# Sheet1.net
KiCad netlist of a schematic drawn in Altium Designer
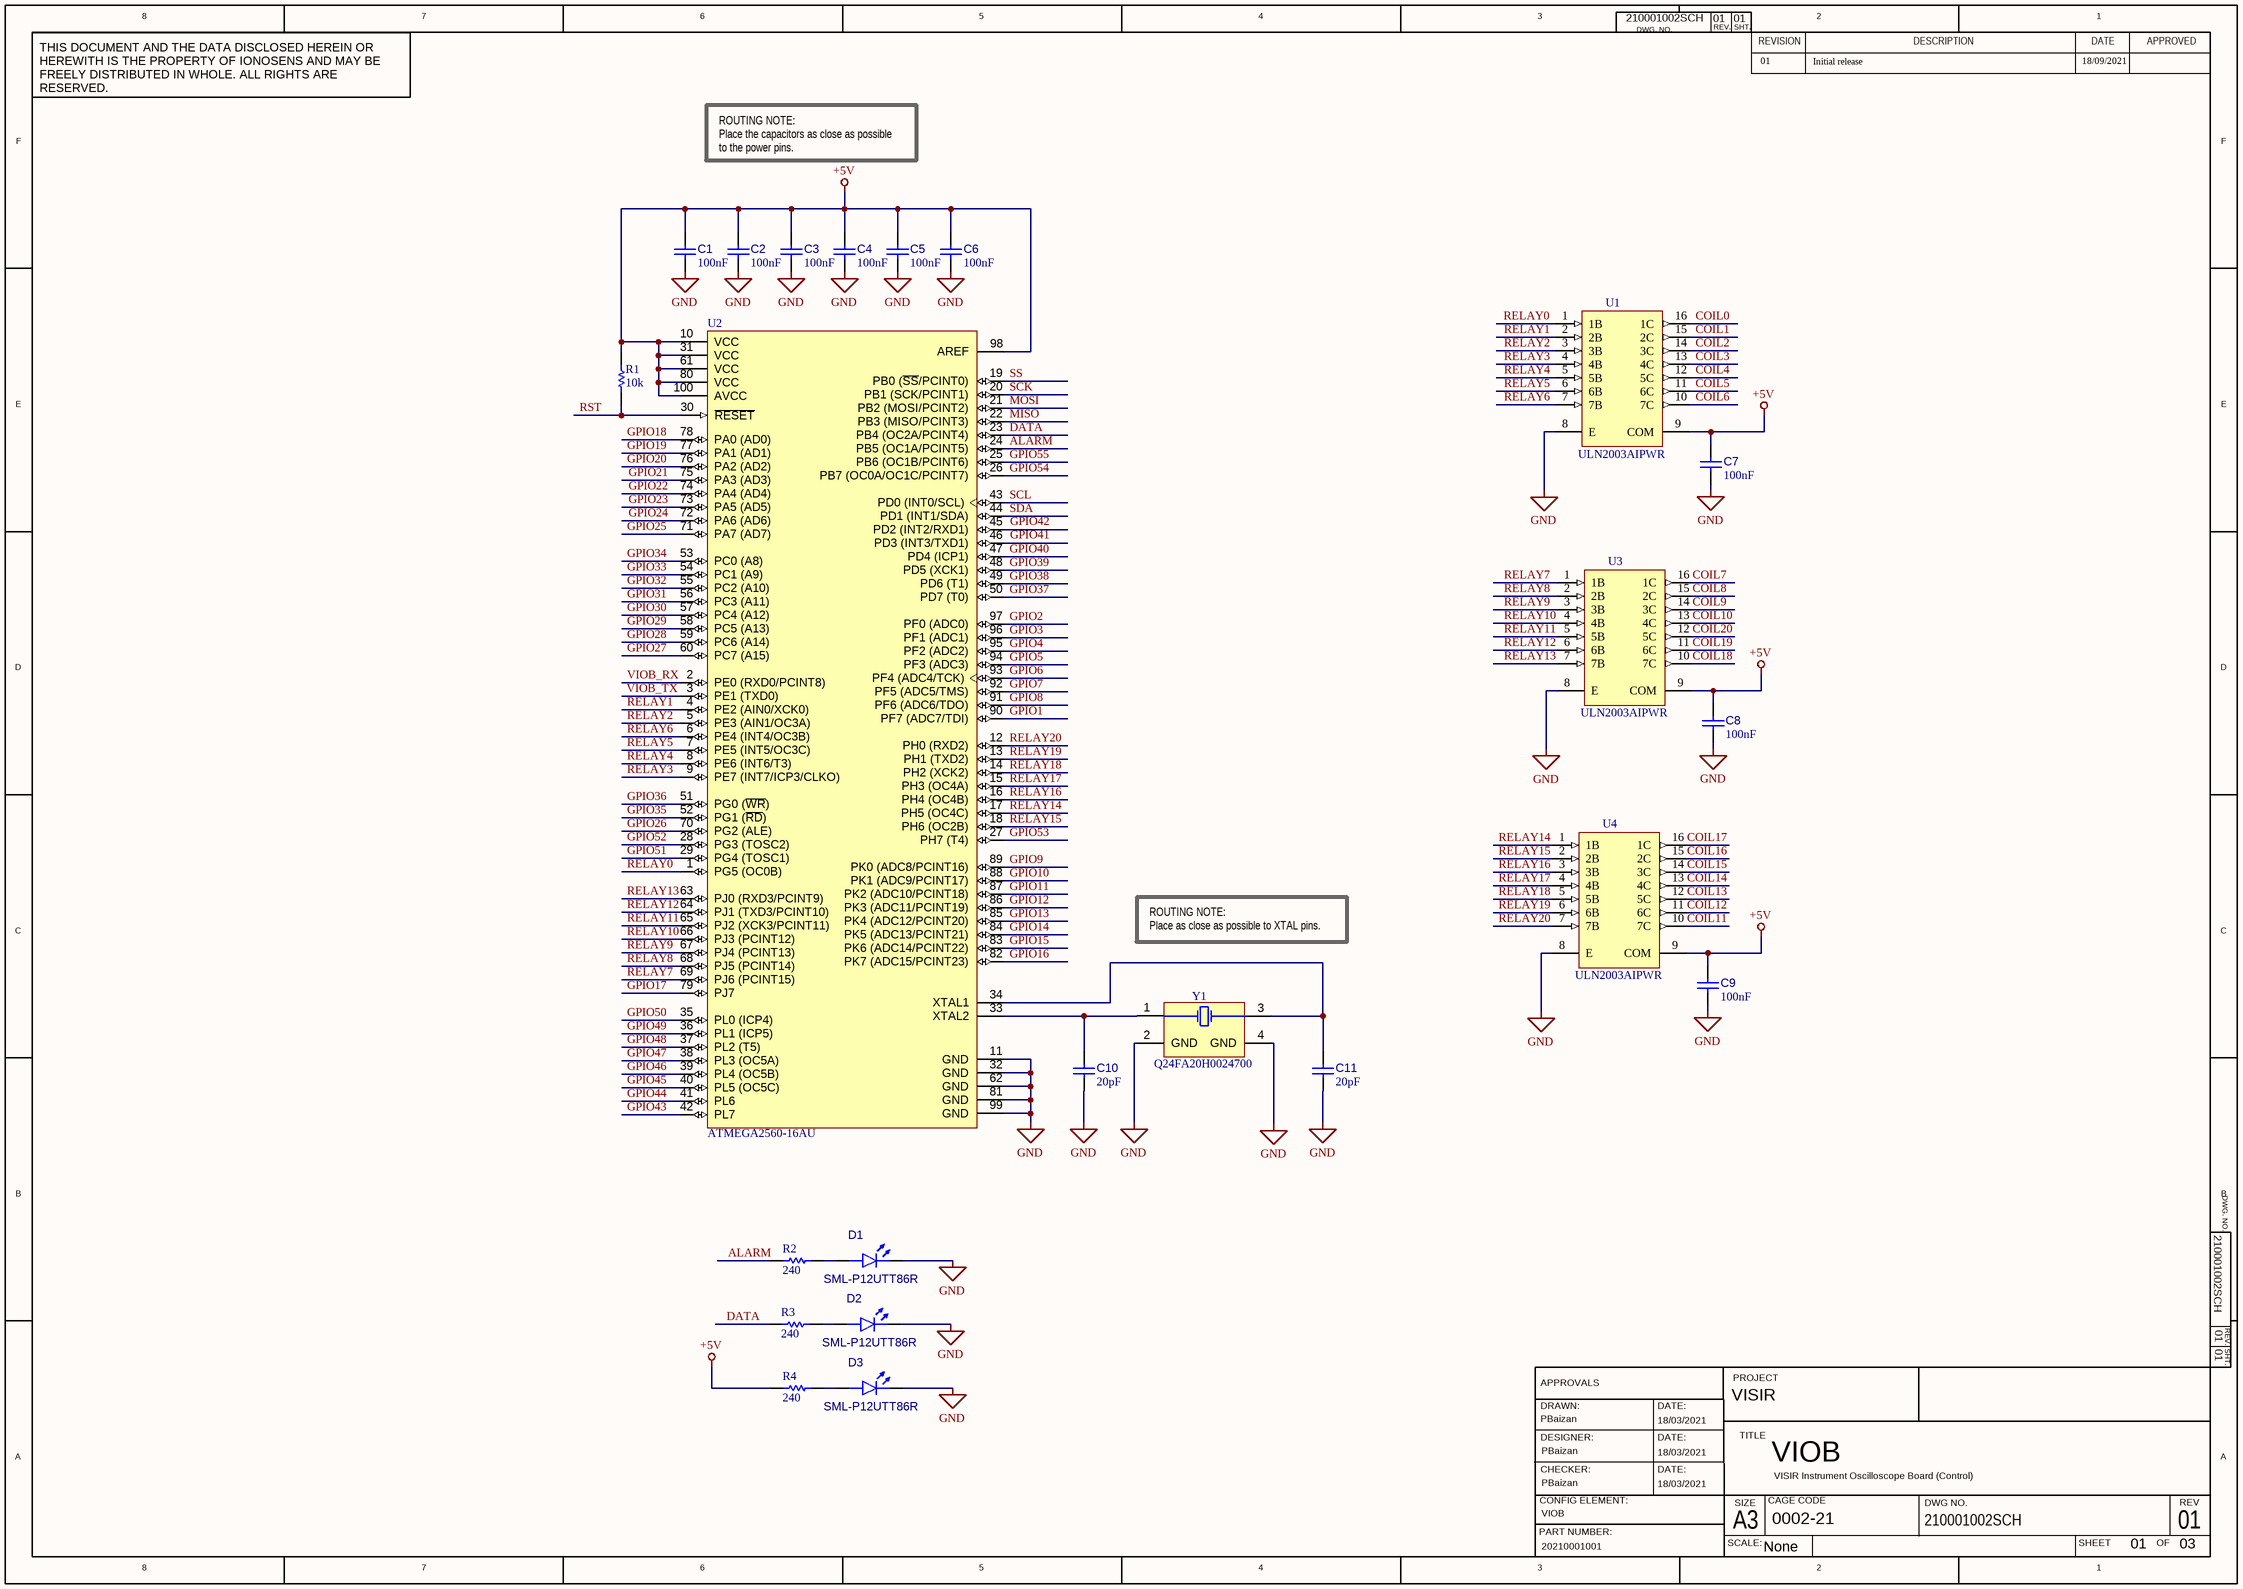
[diagram p0: Sheet1.SchDoc]

(export (version "E")
  (design (tool "Eeschema 10.0.6"))
  (components
    (comp (ref "C1")
      (value "100nF")
      (footprint "CAPC1005X06M")
      (description "Cap Ceramic 100nF 50V X7R 5% SMD 0402 125°C")
      (fields (field (name "TOLERANCE") "5%") (field (name "MANUFACTURER") "YAGEO"))
      (libsource (lib "<Company> Server") (part "CAP-NP-2"))
    )
    (comp (ref "C2")
      (value "100nF")
      (footprint "CAPC1005X06M")
      (description "Cap Ceramic 100nF 50V X7R 5% SMD 0402 125°C")
      (fields (field (name "TOLERANCE") "5%") (field (name "MANUFACTURER") "YAGEO"))
      (libsource (lib "<Company> Server") (part "CAP-NP-2"))
    )
    (comp (ref "C3")
      (value "100nF")
      (footprint "CAPC1005X06M")
      (description "Cap Ceramic 100nF 50V X7R 5% SMD 0402 125°C")
      (fields (field (name "TOLERANCE") "5%") (field (name "MANUFACTURER") "YAGEO"))
      (libsource (lib "<Company> Server") (part "CAP-NP-2"))
    )
    (comp (ref "C4")
      (value "100nF")
      (footprint "CAPC1005X06M")
      (description "Cap Ceramic 100nF 50V X7R 5% SMD 0402 125°C")
      (fields (field (name "TOLERANCE") "5%") (field (name "MANUFACTURER") "YAGEO"))
      (libsource (lib "<Company> Server") (part "CAP-NP-2"))
    )
    (comp (ref "C5")
      (value "100nF")
      (footprint "CAPC1005X06M")
      (description "Cap Ceramic 100nF 50V X7R 5% SMD 0402 125°C")
      (fields (field (name "TOLERANCE") "5%") (field (name "MANUFACTURER") "YAGEO"))
      (libsource (lib "<Company> Server") (part "CAP-NP-2"))
    )
    (comp (ref "C6")
      (value "100nF")
      (footprint "CAPC1005X06M")
      (description "Cap Ceramic 100nF 50V X7R 5% SMD 0402 125°C")
      (fields (field (name "TOLERANCE") "5%") (field (name "MANUFACTURER") "YAGEO"))
      (libsource (lib "<Company> Server") (part "CAP-NP-2"))
    )
    (comp (ref "C7")
      (value "100nF")
      (footprint "CAPC1005X06M")
      (description "Cap Ceramic 100nF 50V X7R 5% SMD 0402 125°C")
      (fields (field (name "TOLERANCE") "5%") (field (name "MANUFACTURER") "YAGEO"))
      (libsource (lib "<Company> Server") (part "CAP-NP-2"))
    )
    (comp (ref "C8")
      (value "100nF")
      (footprint "CAPC1005X06M")
      (description "Cap Ceramic 100nF 50V X7R 5% SMD 0402 125°C")
      (fields (field (name "TOLERANCE") "5%") (field (name "MANUFACTURER") "YAGEO"))
      (libsource (lib "<Company> Server") (part "CAP-NP-2"))
    )
    (comp (ref "C9")
      (value "100nF")
      (footprint "CAPC1005X06M")
      (description "Cap Ceramic 100nF 50V X7R 5% SMD 0402 125°C")
      (fields (field (name "TOLERANCE") "5%") (field (name "MANUFACTURER") "YAGEO"))
      (libsource (lib "<Company> Server") (part "CAP-NP-2"))
    )
    (comp (ref "C10")
      (value "20pF")
      (footprint "CAPC1005X06M")
      (description "Cap Ceramic 20pF 50V C0G 5% SMD 0402 125°C")
      (fields (field (name "MANUFACTURER") "YAGEO") (field (name "TOLERANCE") "5%"))
      (libsource (lib "<Company> Server") (part "CAP-NP-2"))
    )
    (comp (ref "C11")
      (value "20pF")
      (footprint "CAPC1005X06M")
      (description "Cap Ceramic 20pF 50V C0G 5% SMD 0402 125°C")
      (fields (field (name "MANUFACTURER") "YAGEO") (field (name "TOLERANCE") "5%"))
      (libsource (lib "<Company> Server") (part "CAP-NP-2"))
    )
    (comp (ref "D1")
      (value "SML-P12UTT86R")
      (footprint "DIOC1005X02R")
      (description "Led red 0402")
      (fields (field (name "MANUFACTURER") "ROHM"))
      (libsource (lib "<Company> Server") (part "LED"))
    )
    (comp (ref "D2")
      (value "SML-P12UTT86R")
      (footprint "DIOC1005X02R")
      (description "Led red 0402")
      (fields (field (name "MANUFACTURER") "ROHM"))
      (libsource (lib "<Company> Server") (part "LED"))
    )
    (comp (ref "D3")
      (value "SML-P12UTT86R")
      (footprint "DIOC1005X02R")
      (description "Led red 0402")
      (fields (field (name "MANUFACTURER") "ROHM"))
      (libsource (lib "<Company> Server") (part "LED"))
    )
    (comp (ref "R1")
      (value "10k")
      (footprint "RESC1005X04M")
      (description "RES SMD 10K OHM 1% 1/16W 0402")
      (fields (field (name "MANUFACTURER") "Yageo") (field (name "TOLERANCE") "1%"))
      (libsource (lib "<Company> Server") (part "Resistor"))
    )
    (comp (ref "R2")
      (value "240")
      (footprint "RESC1005X04M")
      (description "RES SMD 240 OHM 1% 1/16W 0402")
      (fields (field (name "MANUFACTURER") "Yageo") (field (name "TOLERANCE") "1%"))
      (libsource (lib "<Company> Server") (part "Resistor"))
    )
    (comp (ref "R3")
      (value "240")
      (footprint "RESC1005X04M")
      (description "RES SMD 240 OHM 1% 1/16W 0402")
      (fields (field (name "MANUFACTURER") "Yageo") (field (name "TOLERANCE") "1%"))
      (libsource (lib "<Company> Server") (part "Resistor"))
    )
    (comp (ref "R4")
      (value "240")
      (footprint "RESC1005X04M")
      (description "RES SMD 240 OHM 1% 1/16W 0402")
      (fields (field (name "MANUFACTURER") "Yageo") (field (name "TOLERANCE") "1%"))
      (libsource (lib "<Company> Server") (part "Resistor"))
    )
    (comp (ref "U1")
      (value "ULN2003AIPWR")
      (footprint "TSOP65P640X120-16M")
      (description "50-V, 7-ch darlington transistor array, -40 to 105C 16-TSSOP -40 to 105")
      (fields (field (name "MANUFACTURER") "Texas Instruments"))
      (libsource (lib "<Company> Server") (part "ULN2003AIPWR"))
    )
    (comp (ref "U2")
      (value "ATMEGA2560-16AU")
      (footprint "ATML-100A_M")
      (description "AVR ATmega Microcontroller 8-bit 16MHz 256KB FLASH TQFP100")
      (fields (field (name "MANUFACTURER") "Microchip"))
      (libsource (lib "<Company> Server") (part "ATML-ATMEGA1280_2560-100A"))
    )
    (comp (ref "U3")
      (value "ULN2003AIPWR")
      (footprint "TSOP65P640X120-16M")
      (description "50-V, 7-ch darlington transistor array, -40 to 105C 16-TSSOP -40 to 105")
      (fields (field (name "MANUFACTURER") "Texas Instruments"))
      (libsource (lib "<Company> Server") (part "ULN2003AIPWR"))
    )
    (comp (ref "U4")
      (value "ULN2003AIPWR")
      (footprint "TSOP65P640X120-16M")
      (description "50-V, 7-ch darlington transistor array, -40 to 105C 16-TSSOP -40 to 105")
      (fields (field (name "MANUFACTURER") "Texas Instruments"))
      (libsource (lib "<Company> Server") (part "ULN2003AIPWR"))
    )
    (comp (ref "Y1")
      (value "Q24FA20H0024700")
      (footprint "FA-20H")
      (description "16MHz ±10ppm 16pF 80Ω SMD-2520_4P")
      (fields (field (name "MANUFACTURER") "SEIKO-EPSON"))
      (libsource (lib "<Company> Server") (part "XTAL - 4"))
    )
  )
  (nets
    (net (code "1") (name "+5V") (class "Default")
      (node (ref "C1") (pin "2") (pinfunction "2_2") (pintype "passive"))
      (node (ref "C2") (pin "2") (pinfunction "2_2") (pintype "passive"))
      (node (ref "C3") (pin "2") (pinfunction "2_2") (pintype "passive"))
      (node (ref "C4") (pin "2") (pinfunction "2_2") (pintype "passive"))
      (node (ref "C5") (pin "2") (pinfunction "2_2") (pintype "passive"))
      (node (ref "C6") (pin "2") (pinfunction "2_2") (pintype "passive"))
      (node (ref "C7") (pin "2") (pinfunction "2_2") (pintype "passive"))
      (node (ref "C8") (pin "2") (pinfunction "2_2") (pintype "passive"))
      (node (ref "C9") (pin "2") (pinfunction "2_2") (pintype "passive"))
      (node (ref "R1") (pin "2") (pinfunction "2_2") (pintype "passive"))
      (node (ref "R4") (pin "1") (pinfunction "1_1") (pintype "passive"))
      (node (ref "U1") (pin "9") (pinfunction "COM_9") (pintype "passive"))
      (node (ref "U2") (pin "10") (pinfunction "VCC_10") (pintype "power_in"))
      (node (ref "U2") (pin "100") (pinfunction "AVCC_100") (pintype "power_in"))
      (node (ref "U2") (pin "31") (pinfunction "VCC_31") (pintype "power_in"))
      (node (ref "U2") (pin "61") (pinfunction "VCC_61") (pintype "power_in"))
      (node (ref "U2") (pin "80") (pinfunction "VCC_80") (pintype "power_in"))
      (node (ref "U2") (pin "98") (pinfunction "AREF_98") (pintype "passive"))
      (node (ref "U3") (pin "9") (pinfunction "COM_9") (pintype "passive"))
      (node (ref "U4") (pin "9") (pinfunction "COM_9") (pintype "passive"))
    )
    (net (code "2") (name "/ALARM") (class "Default")
      (node (ref "R2") (pin "1") (pinfunction "1_1") (pintype "passive"))
      (node (ref "U2") (pin "24") (pinfunction "PB5_(OC1A/PCINT5)_24") (pintype "bidirectional"))
    )
    (net (code "3") (name "/COIL0") (class "Default")
      (node (ref "U1") (pin "16") (pinfunction "1C_16") (pintype "output"))
    )
    (net (code "4") (name "/COIL1") (class "Default")
      (node (ref "U1") (pin "15") (pinfunction "2C_15") (pintype "output"))
    )
    (net (code "5") (name "/COIL2") (class "Default")
      (node (ref "U1") (pin "14") (pinfunction "3C_14") (pintype "output"))
    )
    (net (code "6") (name "/COIL3") (class "Default")
      (node (ref "U1") (pin "13") (pinfunction "4C_13") (pintype "output"))
    )
    (net (code "7") (name "/COIL4") (class "Default")
      (node (ref "U1") (pin "12") (pinfunction "5C_12") (pintype "output"))
    )
    (net (code "8") (name "/COIL5") (class "Default")
      (node (ref "U1") (pin "11") (pinfunction "6C_11") (pintype "output"))
    )
    (net (code "9") (name "/COIL6") (class "Default")
      (node (ref "U1") (pin "10") (pinfunction "7C_10") (pintype "output"))
    )
    (net (code "10") (name "/COIL7") (class "Default")
      (node (ref "U3") (pin "16") (pinfunction "1C_16") (pintype "output"))
    )
    (net (code "11") (name "/COIL8") (class "Default")
      (node (ref "U3") (pin "15") (pinfunction "2C_15") (pintype "output"))
    )
    (net (code "12") (name "/COIL9") (class "Default")
      (node (ref "U3") (pin "14") (pinfunction "3C_14") (pintype "output"))
    )
    (net (code "13") (name "/COIL10") (class "Default")
      (node (ref "U3") (pin "13") (pinfunction "4C_13") (pintype "output"))
    )
    (net (code "14") (name "/COIL11") (class "Default")
      (node (ref "U4") (pin "10") (pinfunction "7C_10") (pintype "output"))
    )
    (net (code "15") (name "/COIL12") (class "Default")
      (node (ref "U4") (pin "11") (pinfunction "6C_11") (pintype "output"))
    )
    (net (code "16") (name "/COIL13") (class "Default")
      (node (ref "U4") (pin "12") (pinfunction "5C_12") (pintype "output"))
    )
    (net (code "17") (name "/COIL14") (class "Default")
      (node (ref "U4") (pin "13") (pinfunction "4C_13") (pintype "output"))
    )
    (net (code "18") (name "/COIL15") (class "Default")
      (node (ref "U4") (pin "14") (pinfunction "3C_14") (pintype "output"))
    )
    (net (code "19") (name "/COIL16") (class "Default")
      (node (ref "U4") (pin "15") (pinfunction "2C_15") (pintype "output"))
    )
    (net (code "20") (name "/COIL17") (class "Default")
      (node (ref "U4") (pin "16") (pinfunction "1C_16") (pintype "output"))
    )
    (net (code "21") (name "/COIL18") (class "Default")
      (node (ref "U3") (pin "10") (pinfunction "7C_10") (pintype "output"))
    )
    (net (code "22") (name "/COIL19") (class "Default")
      (node (ref "U3") (pin "11") (pinfunction "6C_11") (pintype "output"))
    )
    (net (code "23") (name "/COIL20") (class "Default")
      (node (ref "U3") (pin "12") (pinfunction "5C_12") (pintype "output"))
    )
    (net (code "24") (name "/DATA") (class "Default")
      (node (ref "R3") (pin "1") (pinfunction "1_1") (pintype "passive"))
      (node (ref "U2") (pin "23") (pinfunction "PB4_(OC2A/PCINT4)_23") (pintype "bidirectional"))
    )
    (net (code "25") (name "/GPIO1") (class "Default")
      (node (ref "U2") (pin "90") (pinfunction "PF7_(ADC7/TDI)_90") (pintype "bidirectional"))
    )
    (net (code "26") (name "/GPIO2") (class "Default")
      (node (ref "U2") (pin "97") (pinfunction "PF0_(ADC0)_97") (pintype "bidirectional"))
    )
    (net (code "27") (name "/GPIO3") (class "Default")
      (node (ref "U2") (pin "96") (pinfunction "PF1_(ADC1)_96") (pintype "bidirectional"))
    )
    (net (code "28") (name "/GPIO4") (class "Default")
      (node (ref "U2") (pin "95") (pinfunction "PF2_(ADC2)_95") (pintype "bidirectional"))
    )
    (net (code "29") (name "/GPIO5") (class "Default")
      (node (ref "U2") (pin "94") (pinfunction "PF3_(ADC3)_94") (pintype "bidirectional"))
    )
    (net (code "30") (name "/GPIO6") (class "Default")
      (node (ref "U2") (pin "93") (pinfunction "PF4_(ADC4/TCK)_93") (pintype "bidirectional"))
    )
    (net (code "31") (name "/GPIO7") (class "Default")
      (node (ref "U2") (pin "92") (pinfunction "PF5_(ADC5/TMS)_92") (pintype "bidirectional"))
    )
    (net (code "32") (name "/GPIO8") (class "Default")
      (node (ref "U2") (pin "91") (pinfunction "PF6_(ADC6/TDO)_91") (pintype "bidirectional"))
    )
    (net (code "33") (name "/GPIO9") (class "Default")
      (node (ref "U2") (pin "89") (pinfunction "PK0_(ADC8/PCINT16)_89") (pintype "bidirectional"))
    )
    (net (code "34") (name "/GPIO10") (class "Default")
      (node (ref "U2") (pin "88") (pinfunction "PK1_(ADC9/PCINT17)_88") (pintype "bidirectional"))
    )
    (net (code "35") (name "/GPIO11") (class "Default")
      (node (ref "U2") (pin "87") (pinfunction "PK2_(ADC10/PCINT18)_87") (pintype "bidirectional"))
    )
    (net (code "36") (name "/GPIO12") (class "Default")
      (node (ref "U2") (pin "86") (pinfunction "PK3_(ADC11/PCINT19)_86") (pintype "bidirectional"))
    )
    (net (code "37") (name "/GPIO13") (class "Default")
      (node (ref "U2") (pin "85") (pinfunction "PK4_(ADC12/PCINT20)_85") (pintype "bidirectional"))
    )
    (net (code "38") (name "/GPIO14") (class "Default")
      (node (ref "U2") (pin "84") (pinfunction "PK5_(ADC13/PCINT21)_84") (pintype "bidirectional"))
    )
    (net (code "39") (name "/GPIO15") (class "Default")
      (node (ref "U2") (pin "83") (pinfunction "PK6_(ADC14/PCINT22)_83") (pintype "bidirectional"))
    )
    (net (code "40") (name "/GPIO16") (class "Default")
      (node (ref "U2") (pin "82") (pinfunction "PK7_(ADC15/PCINT23)_82") (pintype "bidirectional"))
    )
    (net (code "41") (name "/GPIO17") (class "Default")
      (node (ref "U2") (pin "79") (pinfunction "PJ7_79") (pintype "bidirectional"))
    )
    (net (code "42") (name "/GPIO18") (class "Default")
      (node (ref "U2") (pin "78") (pinfunction "PA0_(AD0)_78") (pintype "bidirectional"))
    )
    (net (code "43") (name "/GPIO19") (class "Default")
      (node (ref "U2") (pin "77") (pinfunction "PA1_(AD1)_77") (pintype "bidirectional"))
    )
    (net (code "44") (name "/GPIO20") (class "Default")
      (node (ref "U2") (pin "76") (pinfunction "PA2_(AD2)_76") (pintype "bidirectional"))
    )
    (net (code "45") (name "/GPIO21") (class "Default")
      (node (ref "U2") (pin "75") (pinfunction "PA3_(AD3)_75") (pintype "bidirectional"))
    )
    (net (code "46") (name "/GPIO22") (class "Default")
      (node (ref "U2") (pin "74") (pinfunction "PA4_(AD4)_74") (pintype "bidirectional"))
    )
    (net (code "47") (name "/GPIO23") (class "Default")
      (node (ref "U2") (pin "73") (pinfunction "PA5_(AD5)_73") (pintype "bidirectional"))
    )
    (net (code "48") (name "/GPIO24") (class "Default")
      (node (ref "U2") (pin "72") (pinfunction "PA6_(AD6)_72") (pintype "bidirectional"))
    )
    (net (code "49") (name "/GPIO25") (class "Default")
      (node (ref "U2") (pin "71") (pinfunction "PA7_(AD7)_71") (pintype "bidirectional"))
    )
    (net (code "50") (name "/GPIO26") (class "Default")
      (node (ref "U2") (pin "70") (pinfunction "PG2_(ALE)_70") (pintype "bidirectional"))
    )
    (net (code "51") (name "/GPIO27") (class "Default")
      (node (ref "U2") (pin "60") (pinfunction "PC7_(A15)_60") (pintype "bidirectional"))
    )
    (net (code "52") (name "/GPIO28") (class "Default")
      (node (ref "U2") (pin "59") (pinfunction "PC6_(A14)_59") (pintype "bidirectional"))
    )
    (net (code "53") (name "/GPIO29") (class "Default")
      (node (ref "U2") (pin "58") (pinfunction "PC5_(A13)_58") (pintype "bidirectional"))
    )
    (net (code "54") (name "/GPIO30") (class "Default")
      (node (ref "U2") (pin "57") (pinfunction "PC4_(A12)_57") (pintype "bidirectional"))
    )
    (net (code "55") (name "/GPIO31") (class "Default")
      (node (ref "U2") (pin "56") (pinfunction "PC3_(A11)_56") (pintype "bidirectional"))
    )
    (net (code "56") (name "/GPIO32") (class "Default")
      (node (ref "U2") (pin "55") (pinfunction "PC2_(A10)_55") (pintype "bidirectional"))
    )
    (net (code "57") (name "/GPIO33") (class "Default")
      (node (ref "U2") (pin "54") (pinfunction "PC1_(A9)_54") (pintype "bidirectional"))
    )
    (net (code "58") (name "/GPIO34") (class "Default")
      (node (ref "U2") (pin "53") (pinfunction "PC0_(A8)_53") (pintype "bidirectional"))
    )
    (net (code "59") (name "/GPIO35") (class "Default")
      (node (ref "U2") (pin "52") (pinfunction "PG1_(~{RD})_52") (pintype "bidirectional"))
    )
    (net (code "60") (name "/GPIO36") (class "Default")
      (node (ref "U2") (pin "51") (pinfunction "PG0_(~{WR})_51") (pintype "bidirectional"))
    )
    (net (code "61") (name "/GPIO37") (class "Default")
      (node (ref "U2") (pin "50") (pinfunction "PD7_(T0)_50") (pintype "bidirectional"))
    )
    (net (code "62") (name "/GPIO38") (class "Default")
      (node (ref "U2") (pin "49") (pinfunction "PD6_(T1)_49") (pintype "bidirectional"))
    )
    (net (code "63") (name "/GPIO39") (class "Default")
      (node (ref "U2") (pin "48") (pinfunction "PD5_(XCK1)_48") (pintype "bidirectional"))
    )
    (net (code "64") (name "/GPIO40") (class "Default")
      (node (ref "U2") (pin "47") (pinfunction "PD4_(ICP1)_47") (pintype "bidirectional"))
    )
    (net (code "65") (name "/GPIO41") (class "Default")
      (node (ref "U2") (pin "46") (pinfunction "PD3_(INT3/TXD1)_46") (pintype "bidirectional"))
    )
    (net (code "66") (name "/GPIO42") (class "Default")
      (node (ref "U2") (pin "45") (pinfunction "PD2_(INT2/RXD1)_45") (pintype "bidirectional"))
    )
    (net (code "67") (name "/GPIO43") (class "Default")
      (node (ref "U2") (pin "42") (pinfunction "PL7_42") (pintype "bidirectional"))
    )
    (net (code "68") (name "/GPIO44") (class "Default")
      (node (ref "U2") (pin "41") (pinfunction "PL6_41") (pintype "bidirectional"))
    )
    (net (code "69") (name "/GPIO45") (class "Default")
      (node (ref "U2") (pin "40") (pinfunction "PL5_(OC5C)_40") (pintype "bidirectional"))
    )
    (net (code "70") (name "/GPIO46") (class "Default")
      (node (ref "U2") (pin "39") (pinfunction "PL4_(OC5B)_39") (pintype "bidirectional"))
    )
    (net (code "71") (name "/GPIO47") (class "Default")
      (node (ref "U2") (pin "38") (pinfunction "PL3_(OC5A)_38") (pintype "bidirectional"))
    )
    (net (code "72") (name "/GPIO48") (class "Default")
      (node (ref "U2") (pin "37") (pinfunction "PL2_(T5)_37") (pintype "bidirectional"))
    )
    (net (code "73") (name "/GPIO49") (class "Default")
      (node (ref "U2") (pin "36") (pinfunction "PL1_(ICP5)_36") (pintype "bidirectional"))
    )
    (net (code "74") (name "/GPIO50") (class "Default")
      (node (ref "U2") (pin "35") (pinfunction "PL0_(ICP4)_35") (pintype "bidirectional"))
    )
    (net (code "75") (name "/GPIO51") (class "Default")
      (node (ref "U2") (pin "29") (pinfunction "PG4_(TOSC1)_29") (pintype "bidirectional"))
    )
    (net (code "76") (name "/GPIO52") (class "Default")
      (node (ref "U2") (pin "28") (pinfunction "PG3_(TOSC2)_28") (pintype "bidirectional"))
    )
    (net (code "77") (name "/GPIO53") (class "Default")
      (node (ref "U2") (pin "27") (pinfunction "PH7_(T4)_27") (pintype "bidirectional"))
    )
    (net (code "78") (name "/GPIO54") (class "Default")
      (node (ref "U2") (pin "26") (pinfunction "PB7_(OC0A/OC1C/PCINT7)_26") (pintype "bidirectional"))
    )
    (net (code "79") (name "/GPIO55") (class "Default")
      (node (ref "U2") (pin "25") (pinfunction "PB6_(OC1B/PCINT6)_25") (pintype "bidirectional"))
    )
    (net (code "80") (name "/MISO") (class "Default")
      (node (ref "U2") (pin "22") (pinfunction "PB3_(MISO/PCINT3)_22") (pintype "bidirectional"))
    )
    (net (code "81") (name "/MOSI") (class "Default")
      (node (ref "U2") (pin "21") (pinfunction "PB2_(MOSI/PCINT2)_21") (pintype "bidirectional"))
    )
    (net (code "82") (name "/RELAY0") (class "Default")
      (node (ref "U1") (pin "1") (pinfunction "1B_1") (pintype "input"))
      (node (ref "U2") (pin "1") (pinfunction "PG5_(OC0B)_1") (pintype "bidirectional"))
    )
    (net (code "83") (name "/RELAY1") (class "Default")
      (node (ref "U1") (pin "2") (pinfunction "2B_2") (pintype "input"))
      (node (ref "U2") (pin "4") (pinfunction "PE2_(AIN0/XCK0)_4") (pintype "bidirectional"))
    )
    (net (code "84") (name "/RELAY2") (class "Default")
      (node (ref "U1") (pin "3") (pinfunction "3B_3") (pintype "input"))
      (node (ref "U2") (pin "5") (pinfunction "PE3_(AIN1/OC3A)_5") (pintype "bidirectional"))
    )
    (net (code "85") (name "/RELAY3") (class "Default")
      (node (ref "U1") (pin "4") (pinfunction "4B_4") (pintype "input"))
      (node (ref "U2") (pin "9") (pinfunction "PE7_(INT7/ICP3/CLKO)_9") (pintype "bidirectional"))
    )
    (net (code "86") (name "/RELAY4") (class "Default")
      (node (ref "U1") (pin "5") (pinfunction "5B_5") (pintype "input"))
      (node (ref "U2") (pin "8") (pinfunction "PE6_(INT6/T3)_8") (pintype "bidirectional"))
    )
    (net (code "87") (name "/RELAY5") (class "Default")
      (node (ref "U1") (pin "6") (pinfunction "6B_6") (pintype "input"))
      (node (ref "U2") (pin "7") (pinfunction "PE5_(INT5/OC3C)_7") (pintype "bidirectional"))
    )
    (net (code "88") (name "/RELAY6") (class "Default")
      (node (ref "U1") (pin "7") (pinfunction "7B_7") (pintype "input"))
      (node (ref "U2") (pin "6") (pinfunction "PE4_(INT4/OC3B)_6") (pintype "bidirectional"))
    )
    (net (code "89") (name "/RELAY7") (class "Default")
      (node (ref "U2") (pin "69") (pinfunction "PJ6_(PCINT15)_69") (pintype "bidirectional"))
      (node (ref "U3") (pin "1") (pinfunction "1B_1") (pintype "input"))
    )
    (net (code "90") (name "/RELAY8") (class "Default")
      (node (ref "U2") (pin "68") (pinfunction "PJ5_(PCINT14)_68") (pintype "bidirectional"))
      (node (ref "U3") (pin "2") (pinfunction "2B_2") (pintype "input"))
    )
    (net (code "91") (name "/RELAY9") (class "Default")
      (node (ref "U2") (pin "67") (pinfunction "PJ4_(PCINT13)_67") (pintype "bidirectional"))
      (node (ref "U3") (pin "3") (pinfunction "3B_3") (pintype "input"))
    )
    (net (code "92") (name "/RELAY10") (class "Default")
      (node (ref "U2") (pin "66") (pinfunction "PJ3_(PCINT12)_66") (pintype "bidirectional"))
      (node (ref "U3") (pin "4") (pinfunction "4B_4") (pintype "input"))
    )
    (net (code "93") (name "/RELAY11") (class "Default")
      (node (ref "U2") (pin "65") (pinfunction "PJ2_(XCK3/PCINT11)_65") (pintype "bidirectional"))
      (node (ref "U3") (pin "5") (pinfunction "5B_5") (pintype "input"))
    )
    (net (code "94") (name "/RELAY12") (class "Default")
      (node (ref "U2") (pin "64") (pinfunction "PJ1_(TXD3/PCINT10)_64") (pintype "bidirectional"))
      (node (ref "U3") (pin "6") (pinfunction "6B_6") (pintype "input"))
    )
    (net (code "95") (name "/RELAY13") (class "Default")
      (node (ref "U2") (pin "63") (pinfunction "PJ0_(RXD3/PCINT9)_63") (pintype "bidirectional"))
      (node (ref "U3") (pin "7") (pinfunction "7B_7") (pintype "input"))
    )
    (net (code "96") (name "/RELAY14") (class "Default")
      (node (ref "U2") (pin "17") (pinfunction "PH5_(OC4C)_17") (pintype "bidirectional"))
      (node (ref "U4") (pin "1") (pinfunction "1B_1") (pintype "input"))
    )
    (net (code "97") (name "/RELAY15") (class "Default")
      (node (ref "U2") (pin "18") (pinfunction "PH6_(OC2B)_18") (pintype "bidirectional"))
      (node (ref "U4") (pin "2") (pinfunction "2B_2") (pintype "input"))
    )
    (net (code "98") (name "/RELAY16") (class "Default")
      (node (ref "U2") (pin "16") (pinfunction "PH4_(OC4B)_16") (pintype "bidirectional"))
      (node (ref "U4") (pin "3") (pinfunction "3B_3") (pintype "input"))
    )
    (net (code "99") (name "/RELAY17") (class "Default")
      (node (ref "U2") (pin "15") (pinfunction "PH3_(OC4A)_15") (pintype "bidirectional"))
      (node (ref "U4") (pin "4") (pinfunction "4B_4") (pintype "input"))
    )
    (net (code "100") (name "/RELAY18") (class "Default")
      (node (ref "U2") (pin "14") (pinfunction "PH2_(XCK2)_14") (pintype "bidirectional"))
      (node (ref "U4") (pin "5") (pinfunction "5B_5") (pintype "input"))
    )
    (net (code "101") (name "/RELAY19") (class "Default")
      (node (ref "U2") (pin "13") (pinfunction "PH1_(TXD2)_13") (pintype "bidirectional"))
      (node (ref "U4") (pin "6") (pinfunction "6B_6") (pintype "input"))
    )
    (net (code "102") (name "/RELAY20") (class "Default")
      (node (ref "U2") (pin "12") (pinfunction "PH0_(RXD2)_12") (pintype "bidirectional"))
      (node (ref "U4") (pin "7") (pinfunction "7B_7") (pintype "input"))
    )
    (net (code "103") (name "/RST") (class "Default")
      (node (ref "R1") (pin "1") (pinfunction "1_1") (pintype "passive"))
      (node (ref "U2") (pin "30") (pinfunction "~{RESET}_30") (pintype "input"))
    )
    (net (code "104") (name "/SCK") (class "Default")
      (node (ref "U2") (pin "20") (pinfunction "PB1_(SCK/PCINT1)_20") (pintype "bidirectional"))
    )
    (net (code "105") (name "/SCL") (class "Default")
      (node (ref "U2") (pin "43") (pinfunction "PD0_(INT0/SCL)_43") (pintype "bidirectional"))
    )
    (net (code "106") (name "/SDA") (class "Default")
      (node (ref "U2") (pin "44") (pinfunction "PD1_(INT1/SDA)_44") (pintype "bidirectional"))
    )
    (net (code "107") (name "/SS") (class "Default")
      (node (ref "U2") (pin "19") (pinfunction "PB0_(~{SS}/PCINT0)_19") (pintype "bidirectional"))
    )
    (net (code "108") (name "/VIOB_RX") (class "Default")
      (node (ref "U2") (pin "2") (pinfunction "PE0_(RXD0/PCINT8)_2") (pintype "bidirectional"))
    )
    (net (code "109") (name "/VIOB_TX") (class "Default")
      (node (ref "U2") (pin "3") (pinfunction "PE1_(TXD0)_3") (pintype "bidirectional"))
    )
    (net (code "110") (name "GND") (class "Default")
      (node (ref "C1") (pin "1") (pinfunction "1_1") (pintype "passive"))
      (node (ref "C10") (pin "1") (pinfunction "1_1") (pintype "passive"))
      (node (ref "C11") (pin "1") (pinfunction "1_1") (pintype "passive"))
      (node (ref "C2") (pin "1") (pinfunction "1_1") (pintype "passive"))
      (node (ref "C3") (pin "1") (pinfunction "1_1") (pintype "passive"))
      (node (ref "C4") (pin "1") (pinfunction "1_1") (pintype "passive"))
      (node (ref "C5") (pin "1") (pinfunction "1_1") (pintype "passive"))
      (node (ref "C6") (pin "1") (pinfunction "1_1") (pintype "passive"))
      (node (ref "C7") (pin "1") (pinfunction "1_1") (pintype "passive"))
      (node (ref "C8") (pin "1") (pinfunction "1_1") (pintype "passive"))
      (node (ref "C9") (pin "1") (pinfunction "1_1") (pintype "passive"))
      (node (ref "D1") (pin "1") (pinfunction "K_1") (pintype "passive"))
      (node (ref "D2") (pin "1") (pinfunction "K_1") (pintype "passive"))
      (node (ref "D3") (pin "1") (pinfunction "K_1") (pintype "passive"))
      (node (ref "U1") (pin "8") (pinfunction "E_8") (pintype "passive"))
      (node (ref "U2") (pin "11") (pinfunction "GND_11") (pintype "power_in"))
      (node (ref "U2") (pin "32") (pinfunction "GND_32") (pintype "power_in"))
      (node (ref "U2") (pin "62") (pinfunction "GND_62") (pintype "power_in"))
      (node (ref "U2") (pin "81") (pinfunction "GND_81") (pintype "power_in"))
      (node (ref "U2") (pin "99") (pinfunction "GND_99") (pintype "power_in"))
      (node (ref "U3") (pin "8") (pinfunction "E_8") (pintype "passive"))
      (node (ref "U4") (pin "8") (pinfunction "E_8") (pintype "passive"))
      (node (ref "Y1") (pin "2") (pinfunction "GND_2") (pintype "power_in"))
      (node (ref "Y1") (pin "4") (pinfunction "GND_4") (pintype "power_in"))
    )
    (net (code "111") (name "Net-(D1-A)") (class "Default")
      (node (ref "D1") (pin "2") (pinfunction "A_2") (pintype "passive"))
      (node (ref "R2") (pin "2") (pinfunction "2_2") (pintype "passive"))
    )
    (net (code "112") (name "Net-(D2-A)") (class "Default")
      (node (ref "D2") (pin "2") (pinfunction "A_2") (pintype "passive"))
      (node (ref "R3") (pin "2") (pinfunction "2_2") (pintype "passive"))
    )
    (net (code "113") (name "Net-(D3-A)") (class "Default")
      (node (ref "D3") (pin "2") (pinfunction "A_2") (pintype "passive"))
      (node (ref "R4") (pin "2") (pinfunction "2_2") (pintype "passive"))
    )
    (net (code "114") (name "Net-(U2-XTAL1)") (class "Default")
      (node (ref "C11") (pin "2") (pinfunction "2_2") (pintype "passive"))
      (node (ref "U2") (pin "34") (pinfunction "XTAL1_34") (pintype "passive"))
      (node (ref "Y1") (pin "3") (pinfunction "X2_3") (pintype "passive"))
    )
    (net (code "115") (name "Net-(U2-XTAL2)") (class "Default")
      (node (ref "C10") (pin "2") (pinfunction "2_2") (pintype "passive"))
      (node (ref "U2") (pin "33") (pinfunction "XTAL2_33") (pintype "passive"))
      (node (ref "Y1") (pin "1") (pinfunction "X1_1") (pintype "passive"))
    )
  )
)
